# W532B.net
KiCad netlist of a schematic drawn in EAGLE
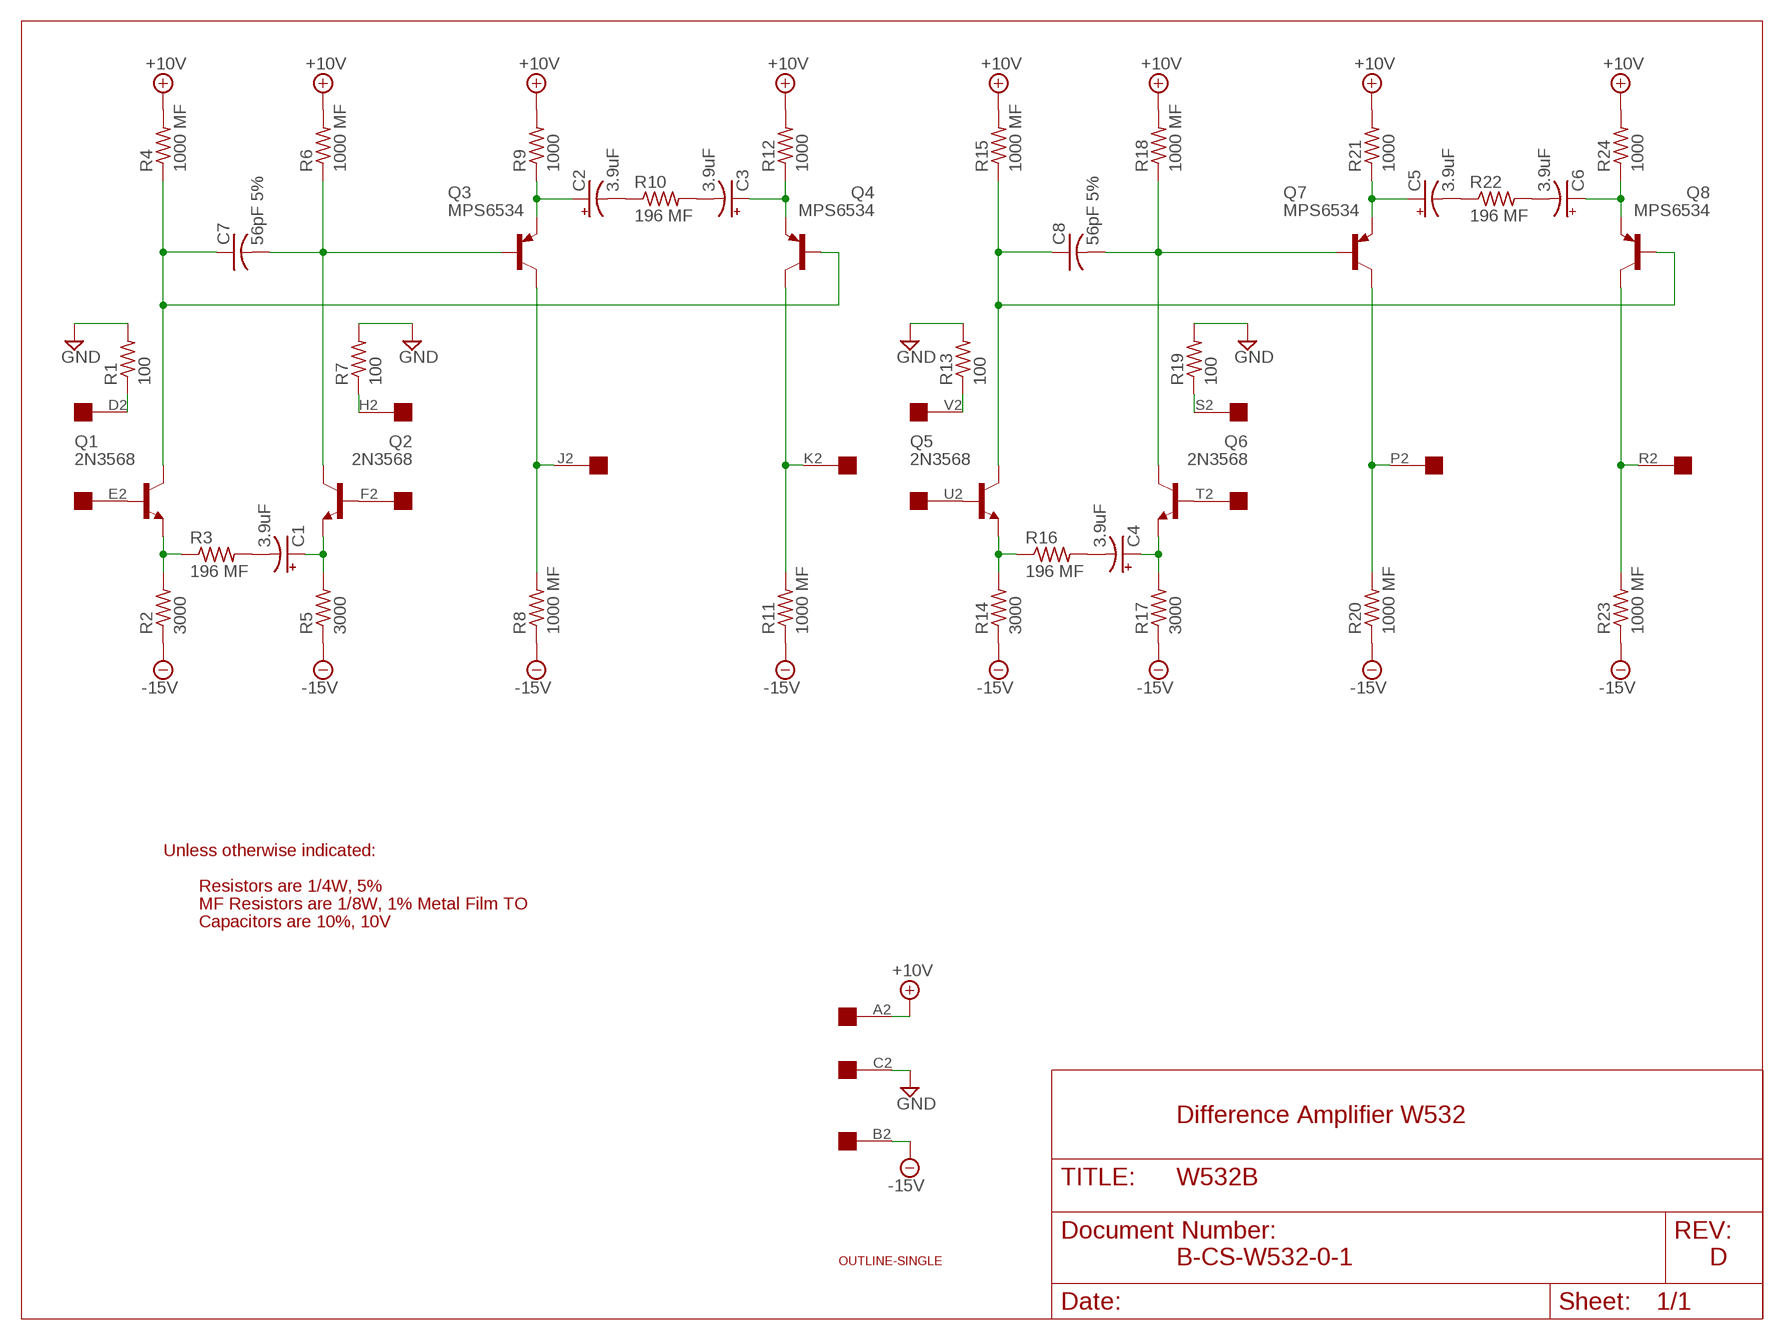
[diagram p0: schematic, sheet 1]

(export (version "E")
  (design (tool "Eeschema 10.0.6"))
  (components
    (comp (ref "C1")
      (value "3.9uF")
      (footprint "eagle-import:E15-5")
      (libsource (lib "eagle-import") (part "CPOL-USE15-5AXIAL"))
    )
    (comp (ref "C2")
      (value "3.9uF")
      (footprint "eagle-import:E15-5")
      (libsource (lib "eagle-import") (part "CPOL-USE15-5AXIAL"))
    )
    (comp (ref "C3")
      (value "3.9uF")
      (footprint "eagle-import:E15-5")
      (libsource (lib "eagle-import") (part "CPOL-USE15-5AXIAL"))
    )
    (comp (ref "C4")
      (value "3.9uF")
      (footprint "eagle-import:E15-5")
      (libsource (lib "eagle-import") (part "CPOL-USE15-5AXIAL"))
    )
    (comp (ref "C5")
      (value "3.9uF")
      (footprint "eagle-import:E15-5")
      (libsource (lib "eagle-import") (part "CPOL-USE15-5AXIAL"))
    )
    (comp (ref "C6")
      (value "3.9uF")
      (footprint "eagle-import:E15-5")
      (libsource (lib "eagle-import") (part "CPOL-USE15-5AXIAL"))
    )
    (comp (ref "C7")
      (value "56pF 5%")
      (footprint "eagle-import:C150-054X183")
      (libsource (lib "eagle-import") (part "C-US150-054X183"))
    )
    (comp (ref "C8")
      (value "56pF 5%")
      (footprint "eagle-import:C150-054X183")
      (libsource (lib "eagle-import") (part "C-US150-054X183"))
    )
    (comp (ref "Q1")
      (value "2N3568")
      (footprint "eagle-import:TO5")
      (libsource (lib "eagle-import") (part "2N2102"))
    )
    (comp (ref "Q2")
      (value "2N3568")
      (footprint "eagle-import:TO5")
      (libsource (lib "eagle-import") (part "2N2102"))
    )
    (comp (ref "Q3")
      (value "MPS6534")
      (footprint "eagle-import:TO39")
      (libsource (lib "eagle-import") (part "2N2904"))
    )
    (comp (ref "Q4")
      (value "MPS6534")
      (footprint "eagle-import:TO39")
      (libsource (lib "eagle-import") (part "2N2904"))
    )
    (comp (ref "Q5")
      (value "2N3568")
      (footprint "eagle-import:TO5")
      (libsource (lib "eagle-import") (part "2N2102"))
    )
    (comp (ref "Q6")
      (value "2N3568")
      (footprint "eagle-import:TO5")
      (libsource (lib "eagle-import") (part "2N2102"))
    )
    (comp (ref "Q7")
      (value "MPS6534")
      (footprint "eagle-import:TO39")
      (libsource (lib "eagle-import") (part "2N2904"))
    )
    (comp (ref "Q8")
      (value "MPS6534")
      (footprint "eagle-import:TO39")
      (libsource (lib "eagle-import") (part "2N2904"))
    )
    (comp (ref "R1")
      (value "100")
      (footprint "eagle-import:0207_10")
      (libsource (lib "eagle-import") (part "R-US_0207/10"))
    )
    (comp (ref "R2")
      (value "3000")
      (footprint "eagle-import:0207_10")
      (libsource (lib "eagle-import") (part "R-US_0207/10"))
    )
    (comp (ref "R3")
      (value "196 MF")
      (footprint "eagle-import:0207_15")
      (libsource (lib "eagle-import") (part "R-US_0207/15"))
    )
    (comp (ref "R4")
      (value "1000 MF")
      (footprint "eagle-import:0207_15")
      (libsource (lib "eagle-import") (part "R-US_0207/15"))
    )
    (comp (ref "R5")
      (value "3000")
      (footprint "eagle-import:0207_10")
      (libsource (lib "eagle-import") (part "R-US_0207/10"))
    )
    (comp (ref "R6")
      (value "1000 MF")
      (footprint "eagle-import:0207_15")
      (libsource (lib "eagle-import") (part "R-US_0207/15"))
    )
    (comp (ref "R7")
      (value "100")
      (footprint "eagle-import:0207_10")
      (libsource (lib "eagle-import") (part "R-US_0207/10"))
    )
    (comp (ref "R8")
      (value "1000 MF")
      (footprint "eagle-import:0207_15")
      (libsource (lib "eagle-import") (part "R-US_0207/15"))
    )
    (comp (ref "R9")
      (value "1000")
      (footprint "eagle-import:0207_10")
      (libsource (lib "eagle-import") (part "R-US_0207/10"))
    )
    (comp (ref "R10")
      (value "196 MF")
      (footprint "eagle-import:0207_15")
      (libsource (lib "eagle-import") (part "R-US_0207/15"))
    )
    (comp (ref "R11")
      (value "1000 MF")
      (footprint "eagle-import:0207_15")
      (libsource (lib "eagle-import") (part "R-US_0207/15"))
    )
    (comp (ref "R12")
      (value "1000")
      (footprint "eagle-import:0207_10")
      (libsource (lib "eagle-import") (part "R-US_0207/10"))
    )
    (comp (ref "R13")
      (value "100")
      (footprint "eagle-import:0207_10")
      (libsource (lib "eagle-import") (part "R-US_0207/10"))
    )
    (comp (ref "R14")
      (value "3000")
      (footprint "eagle-import:0207_10")
      (libsource (lib "eagle-import") (part "R-US_0207/10"))
    )
    (comp (ref "R15")
      (value "1000 MF")
      (footprint "eagle-import:0207_15")
      (libsource (lib "eagle-import") (part "R-US_0207/15"))
    )
    (comp (ref "R16")
      (value "196 MF")
      (footprint "eagle-import:0207_15")
      (libsource (lib "eagle-import") (part "R-US_0207/15"))
    )
    (comp (ref "R17")
      (value "3000")
      (footprint "eagle-import:0207_10")
      (libsource (lib "eagle-import") (part "R-US_0207/10"))
    )
    (comp (ref "R18")
      (value "1000 MF")
      (footprint "eagle-import:0207_15")
      (libsource (lib "eagle-import") (part "R-US_0207/15"))
    )
    (comp (ref "R19")
      (value "100")
      (footprint "eagle-import:0207_10")
      (libsource (lib "eagle-import") (part "R-US_0207/10"))
    )
    (comp (ref "R20")
      (value "1000 MF")
      (footprint "eagle-import:0207_15")
      (libsource (lib "eagle-import") (part "R-US_0207/15"))
    )
    (comp (ref "R21")
      (value "1000")
      (footprint "eagle-import:0207_10")
      (libsource (lib "eagle-import") (part "R-US_0207/10"))
    )
    (comp (ref "R22")
      (value "196 MF")
      (footprint "eagle-import:0207_15")
      (libsource (lib "eagle-import") (part "R-US_0207/15"))
    )
    (comp (ref "R23")
      (value "1000 MF")
      (footprint "eagle-import:0207_15")
      (libsource (lib "eagle-import") (part "R-US_0207/15"))
    )
    (comp (ref "R24")
      (value "1000")
      (footprint "eagle-import:0207_10")
      (libsource (lib "eagle-import") (part "R-US_0207/10"))
    )
    (comp (ref "U$1")
      (value "OUTLINE-SINGLE")
      (footprint "eagle-import:SINGLE")
      (libsource (lib "eagle-import") (part "OUTLINE-SINGLE"))
    )
    (comp (ref "U$2")
      (value "EDGE-1")
      (footprint "eagle-import:EDGE-CON1")
      (libsource (lib "eagle-import") (part "EDGE-1"))
    )
  )
  (nets
    (net (code "1") (name "+10V") (class "Default")
      (node (ref "R12") (pin "2") (pinfunction "2_2") (pintype "passive"))
      (node (ref "R15") (pin "2") (pinfunction "2_2") (pintype "passive"))
      (node (ref "R18") (pin "2") (pinfunction "2_2") (pintype "passive"))
      (node (ref "R21") (pin "2") (pinfunction "2_2") (pintype "passive"))
      (node (ref "R24") (pin "2") (pinfunction "2_2") (pintype "passive"))
      (node (ref "R4") (pin "2") (pinfunction "2_2") (pintype "passive"))
      (node (ref "R6") (pin "2") (pinfunction "2_2") (pintype "passive"))
      (node (ref "R9") (pin "2") (pinfunction "2_2") (pintype "passive"))
      (node (ref "U$2") (pin "A2") (pinfunction "1_A2") (pintype "bidirectional"))
    )
    (net (code "2") (name "-15V") (class "Default")
      (node (ref "R11") (pin "1") (pinfunction "1_1") (pintype "passive"))
      (node (ref "R14") (pin "1") (pinfunction "1_1") (pintype "passive"))
      (node (ref "R17") (pin "1") (pinfunction "1_1") (pintype "passive"))
      (node (ref "R2") (pin "1") (pinfunction "1_1") (pintype "passive"))
      (node (ref "R20") (pin "1") (pinfunction "1_1") (pintype "passive"))
      (node (ref "R23") (pin "1") (pinfunction "1_1") (pintype "passive"))
      (node (ref "R5") (pin "1") (pinfunction "1_1") (pintype "passive"))
      (node (ref "R8") (pin "1") (pinfunction "1_1") (pintype "passive"))
      (node (ref "U$2") (pin "B2") (pinfunction "1_B2") (pintype "bidirectional"))
    )
    (net (code "3") (name "GND") (class "Default")
      (node (ref "R1") (pin "2") (pinfunction "2_2") (pintype "passive"))
      (node (ref "R13") (pin "2") (pinfunction "2_2") (pintype "passive"))
      (node (ref "R19") (pin "2") (pinfunction "2_2") (pintype "passive"))
      (node (ref "R7") (pin "2") (pinfunction "2_2") (pintype "passive"))
      (node (ref "U$2") (pin "C2") (pinfunction "1_C2") (pintype "bidirectional"))
    )
    (net (code "4") (name "Net-(C1-Pad-)") (class "Default")
      (node (ref "C1") (pin "-") (pinfunction "-_-") (pintype "passive"))
      (node (ref "R3") (pin "2") (pinfunction "2_2") (pintype "passive"))
    )
    (net (code "5") (name "Net-(C2-Pad-)") (class "Default")
      (node (ref "C2") (pin "-") (pinfunction "-_-") (pintype "passive"))
      (node (ref "R10") (pin "1") (pinfunction "1_1") (pintype "passive"))
    )
    (net (code "6") (name "Net-(C3-Pad-)") (class "Default")
      (node (ref "C3") (pin "-") (pinfunction "-_-") (pintype "passive"))
      (node (ref "R10") (pin "2") (pinfunction "2_2") (pintype "passive"))
    )
    (net (code "7") (name "Net-(C4-Pad-)") (class "Default")
      (node (ref "C4") (pin "-") (pinfunction "-_-") (pintype "passive"))
      (node (ref "R16") (pin "2") (pinfunction "2_2") (pintype "passive"))
    )
    (net (code "8") (name "Net-(C5-Pad-)") (class "Default")
      (node (ref "C5") (pin "-") (pinfunction "-_-") (pintype "passive"))
      (node (ref "R22") (pin "1") (pinfunction "1_1") (pintype "passive"))
    )
    (net (code "9") (name "Net-(C6-Pad-)") (class "Default")
      (node (ref "C6") (pin "-") (pinfunction "-_-") (pintype "passive"))
      (node (ref "R22") (pin "2") (pinfunction "2_2") (pintype "passive"))
    )
    (net (code "10") (name "Net-(Q1-B)") (class "Default")
      (node (ref "Q1") (pin "2") (pinfunction "B_2") (pintype "passive"))
      (node (ref "U$2") (pin "E2") (pinfunction "1_E2") (pintype "bidirectional"))
    )
    (net (code "11") (name "Net-(Q1-C)") (class "Default")
      (node (ref "C7") (pin "1") (pinfunction "1_1") (pintype "passive"))
      (node (ref "Q1") (pin "3") (pinfunction "C_3") (pintype "passive"))
      (node (ref "Q4") (pin "2") (pinfunction "B_2") (pintype "passive"))
      (node (ref "R4") (pin "1") (pinfunction "1_1") (pintype "passive"))
    )
    (net (code "12") (name "Net-(Q1-E)") (class "Default")
      (node (ref "Q1") (pin "1") (pinfunction "E_1") (pintype "passive"))
      (node (ref "R2") (pin "2") (pinfunction "2_2") (pintype "passive"))
      (node (ref "R3") (pin "1") (pinfunction "1_1") (pintype "passive"))
    )
    (net (code "13") (name "Net-(Q2-B)") (class "Default")
      (node (ref "Q2") (pin "2") (pinfunction "B_2") (pintype "passive"))
      (node (ref "U$2") (pin "F2") (pinfunction "1_F2") (pintype "bidirectional"))
    )
    (net (code "14") (name "Net-(Q2-C)") (class "Default")
      (node (ref "C7") (pin "2") (pinfunction "2_2") (pintype "passive"))
      (node (ref "Q2") (pin "3") (pinfunction "C_3") (pintype "passive"))
      (node (ref "Q3") (pin "2") (pinfunction "B_2") (pintype "passive"))
      (node (ref "R6") (pin "1") (pinfunction "1_1") (pintype "passive"))
    )
    (net (code "15") (name "Net-(Q2-E)") (class "Default")
      (node (ref "C1") (pin "+") (pinfunction "+_+") (pintype "passive"))
      (node (ref "Q2") (pin "1") (pinfunction "E_1") (pintype "passive"))
      (node (ref "R5") (pin "2") (pinfunction "2_2") (pintype "passive"))
    )
    (net (code "16") (name "Net-(Q3-C)") (class "Default")
      (node (ref "Q3") (pin "3") (pinfunction "C_3") (pintype "passive"))
      (node (ref "R8") (pin "2") (pinfunction "2_2") (pintype "passive"))
      (node (ref "U$2") (pin "J2") (pinfunction "1_J2") (pintype "bidirectional"))
    )
    (net (code "17") (name "Net-(Q3-E)") (class "Default")
      (node (ref "C2") (pin "+") (pinfunction "+_+") (pintype "passive"))
      (node (ref "Q3") (pin "1") (pinfunction "E_1") (pintype "passive"))
      (node (ref "R9") (pin "1") (pinfunction "1_1") (pintype "passive"))
    )
    (net (code "18") (name "Net-(Q4-C)") (class "Default")
      (node (ref "Q4") (pin "3") (pinfunction "C_3") (pintype "passive"))
      (node (ref "R11") (pin "2") (pinfunction "2_2") (pintype "passive"))
      (node (ref "U$2") (pin "K2") (pinfunction "1_K2") (pintype "bidirectional"))
    )
    (net (code "19") (name "Net-(Q4-E)") (class "Default")
      (node (ref "C3") (pin "+") (pinfunction "+_+") (pintype "passive"))
      (node (ref "Q4") (pin "1") (pinfunction "E_1") (pintype "passive"))
      (node (ref "R12") (pin "1") (pinfunction "1_1") (pintype "passive"))
    )
    (net (code "20") (name "Net-(Q5-B)") (class "Default")
      (node (ref "Q5") (pin "2") (pinfunction "B_2") (pintype "passive"))
      (node (ref "U$2") (pin "U2") (pinfunction "1_U2") (pintype "bidirectional"))
    )
    (net (code "21") (name "Net-(Q5-C)") (class "Default")
      (node (ref "C8") (pin "1") (pinfunction "1_1") (pintype "passive"))
      (node (ref "Q5") (pin "3") (pinfunction "C_3") (pintype "passive"))
      (node (ref "Q8") (pin "2") (pinfunction "B_2") (pintype "passive"))
      (node (ref "R15") (pin "1") (pinfunction "1_1") (pintype "passive"))
    )
    (net (code "22") (name "Net-(Q5-E)") (class "Default")
      (node (ref "Q5") (pin "1") (pinfunction "E_1") (pintype "passive"))
      (node (ref "R14") (pin "2") (pinfunction "2_2") (pintype "passive"))
      (node (ref "R16") (pin "1") (pinfunction "1_1") (pintype "passive"))
    )
    (net (code "23") (name "Net-(Q6-B)") (class "Default")
      (node (ref "Q6") (pin "2") (pinfunction "B_2") (pintype "passive"))
      (node (ref "U$2") (pin "T2") (pinfunction "1_T2") (pintype "bidirectional"))
    )
    (net (code "24") (name "Net-(Q6-C)") (class "Default")
      (node (ref "C8") (pin "2") (pinfunction "2_2") (pintype "passive"))
      (node (ref "Q6") (pin "3") (pinfunction "C_3") (pintype "passive"))
      (node (ref "Q7") (pin "2") (pinfunction "B_2") (pintype "passive"))
      (node (ref "R18") (pin "1") (pinfunction "1_1") (pintype "passive"))
    )
    (net (code "25") (name "Net-(Q6-E)") (class "Default")
      (node (ref "C4") (pin "+") (pinfunction "+_+") (pintype "passive"))
      (node (ref "Q6") (pin "1") (pinfunction "E_1") (pintype "passive"))
      (node (ref "R17") (pin "2") (pinfunction "2_2") (pintype "passive"))
    )
    (net (code "26") (name "Net-(Q7-C)") (class "Default")
      (node (ref "Q7") (pin "3") (pinfunction "C_3") (pintype "passive"))
      (node (ref "R20") (pin "2") (pinfunction "2_2") (pintype "passive"))
      (node (ref "U$2") (pin "P2") (pinfunction "1_P2") (pintype "bidirectional"))
    )
    (net (code "27") (name "Net-(Q7-E)") (class "Default")
      (node (ref "C5") (pin "+") (pinfunction "+_+") (pintype "passive"))
      (node (ref "Q7") (pin "1") (pinfunction "E_1") (pintype "passive"))
      (node (ref "R21") (pin "1") (pinfunction "1_1") (pintype "passive"))
    )
    (net (code "28") (name "Net-(Q8-C)") (class "Default")
      (node (ref "Q8") (pin "3") (pinfunction "C_3") (pintype "passive"))
      (node (ref "R23") (pin "2") (pinfunction "2_2") (pintype "passive"))
      (node (ref "U$2") (pin "R2") (pinfunction "1_R2") (pintype "bidirectional"))
    )
    (net (code "29") (name "Net-(Q8-E)") (class "Default")
      (node (ref "C6") (pin "+") (pinfunction "+_+") (pintype "passive"))
      (node (ref "Q8") (pin "1") (pinfunction "E_1") (pintype "passive"))
      (node (ref "R24") (pin "1") (pinfunction "1_1") (pintype "passive"))
    )
    (net (code "30") (name "Net-(U$2D-1)") (class "Default")
      (node (ref "R1") (pin "1") (pinfunction "1_1") (pintype "passive"))
      (node (ref "U$2") (pin "D2") (pinfunction "1_D2") (pintype "bidirectional"))
    )
    (net (code "31") (name "Net-(U$2G-1)") (class "Default")
      (node (ref "R7") (pin "1") (pinfunction "1_1") (pintype "passive"))
      (node (ref "U$2") (pin "H2") (pinfunction "1_H2") (pintype "bidirectional"))
    )
    (net (code "32") (name "Net-(U$2O-1)") (class "Default")
      (node (ref "R19") (pin "1") (pinfunction "1_1") (pintype "passive"))
      (node (ref "U$2") (pin "S2") (pinfunction "1_S2") (pintype "bidirectional"))
    )
    (net (code "33") (name "Net-(U$2R-1)") (class "Default")
      (node (ref "R13") (pin "1") (pinfunction "1_1") (pintype "passive"))
      (node (ref "U$2") (pin "V2") (pinfunction "1_V2") (pintype "bidirectional"))
    )
  )
)
